# Symposion_K3_Arduino-Peripherie-IF.net
KiCad netlist of a schematic drawn in EAGLE
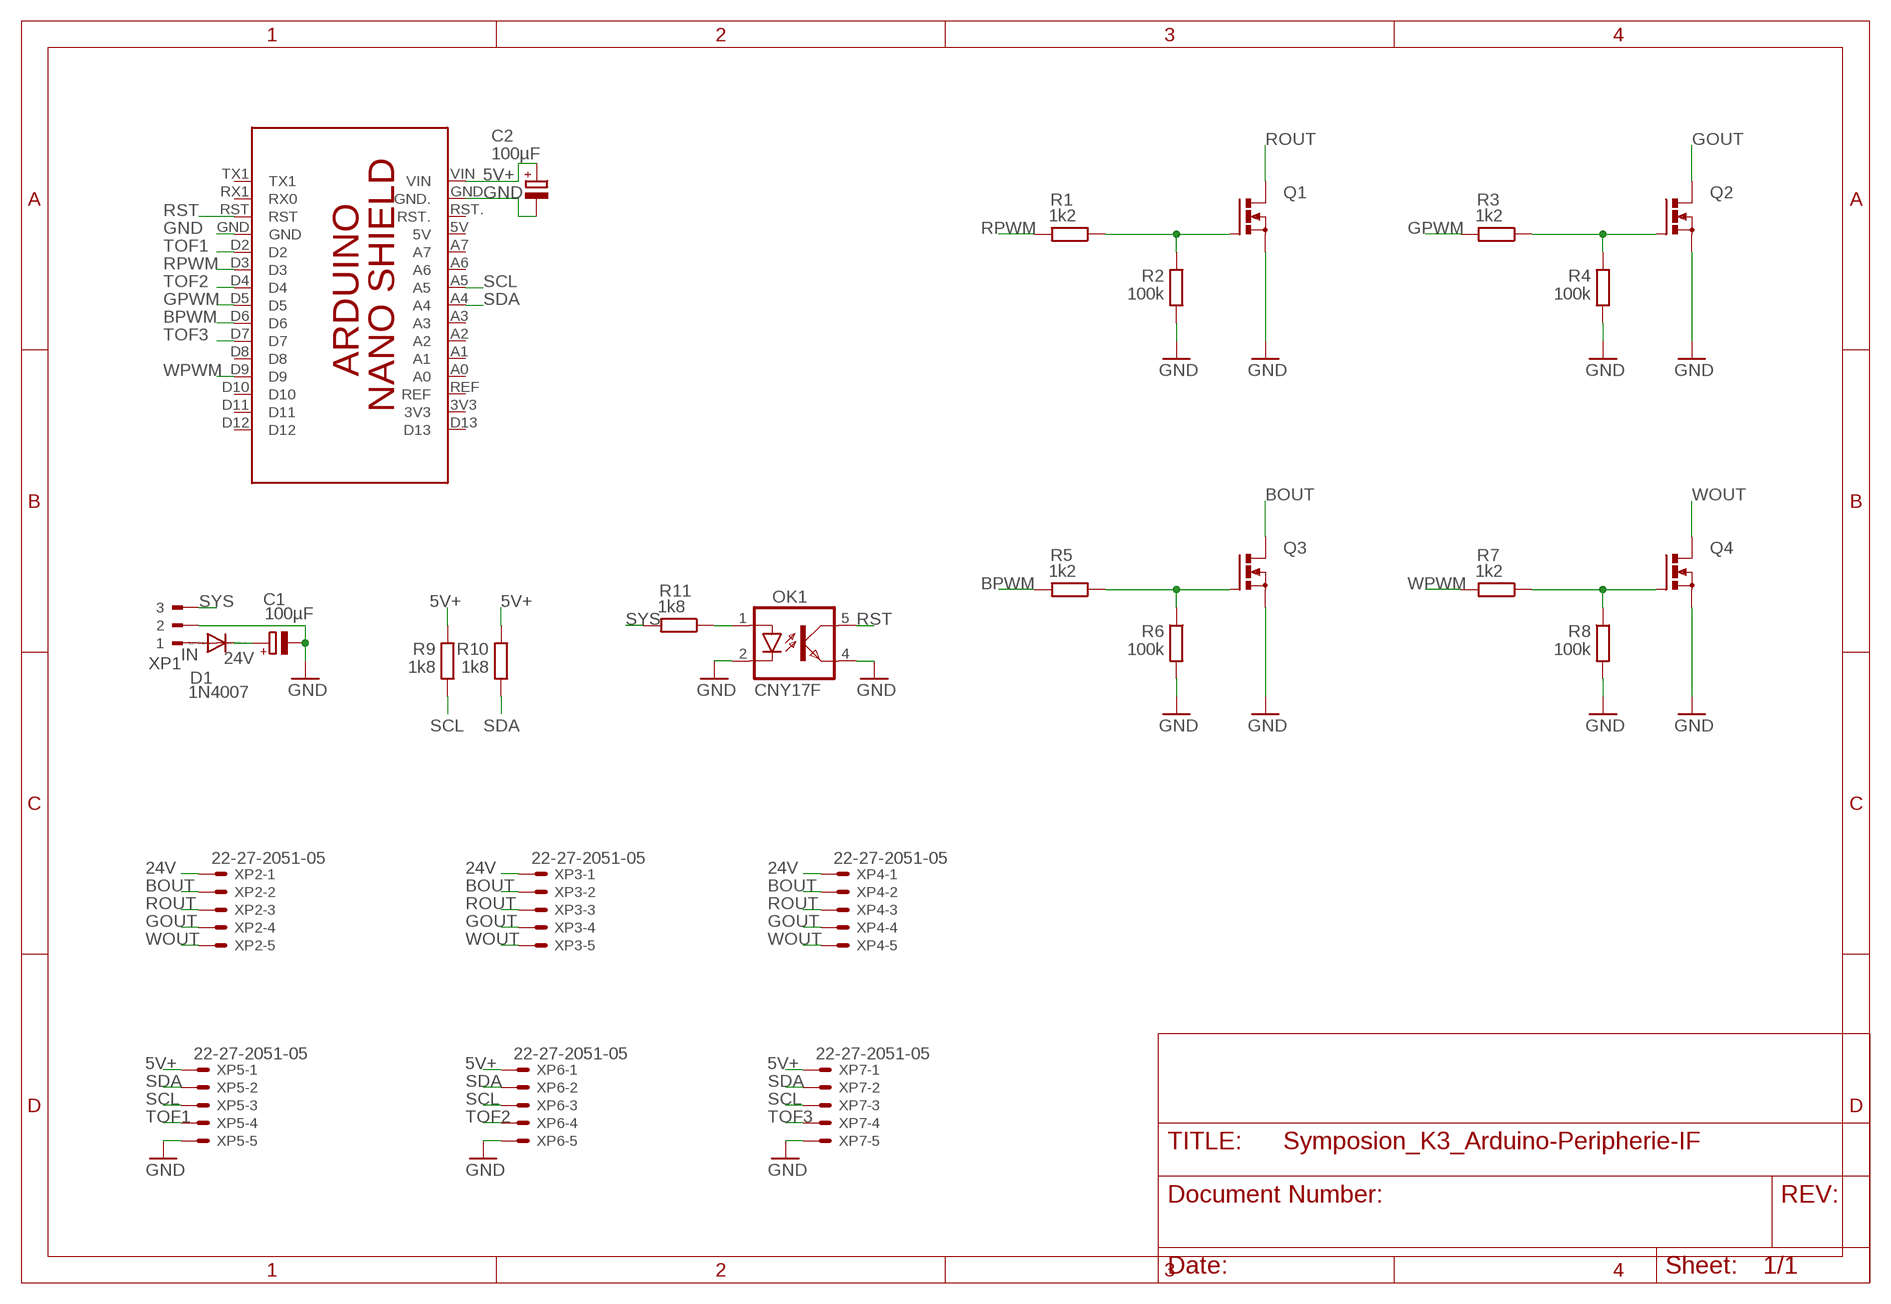
[diagram p0: schematic, sheet 1]

(export (version "E")
  (design (tool "Eeschema 10.0.6"))
  (components
    (comp (ref "C1")
      (value "100µF")
      (footprint "eagle-import:RCL_E5-6")
      (libsource (lib "eagle-import") (part "RCL_CPOL-EUE5-6"))
    )
    (comp (ref "C2")
      (value "100µF")
      (footprint "eagle-import:RCL_E5-6")
      (libsource (lib "eagle-import") (part "RCL_CPOL-EUE5-6"))
    )
    (comp (ref "D1")
      (value "1N4007")
      (footprint "eagle-import:DIODE_F126-10")
      (libsource (lib "eagle-import") (part "DIODE_DIODE-F126-10"))
    )
    (comp (ref "OK1")
      (value "CNY17F")
      (footprint "eagle-import:DIL06")
      (fields (field (name "MF") "VISHAY/TELEFUNKEN") (field (name "MPN") "CNY17F-3"))
      (libsource (lib "eagle-import") (part "CNY17F"))
    )
    (comp (ref "PCB1")
      (value "0_WSH_FAVORITES_ARDUINO_NANO")
      (footprint "eagle-import:0_WSH_FAVORITES_ARDUINO_NANO")
      (libsource (lib "eagle-import") (part "0_WSH_FAVORITES_ARDUINO_NANO"))
    )
    (comp (ref "Q1")
      (value "0_WSH_FAVORITES_BUZ11BV")
      (footprint "eagle-import:0_WSH_FAVORITES_TO220BV")
      (libsource (lib "eagle-import") (part "0_WSH_FAVORITES_BUZ11BV"))
    )
    (comp (ref "Q2")
      (value "0_WSH_FAVORITES_BUZ11BV")
      (footprint "eagle-import:0_WSH_FAVORITES_TO220BV")
      (libsource (lib "eagle-import") (part "0_WSH_FAVORITES_BUZ11BV"))
    )
    (comp (ref "Q3")
      (value "0_WSH_FAVORITES_BUZ11BV")
      (footprint "eagle-import:0_WSH_FAVORITES_TO220BV")
      (libsource (lib "eagle-import") (part "0_WSH_FAVORITES_BUZ11BV"))
    )
    (comp (ref "Q4")
      (value "0_WSH_FAVORITES_BUZ11BV")
      (footprint "eagle-import:0_WSH_FAVORITES_TO220BV")
      (libsource (lib "eagle-import") (part "0_WSH_FAVORITES_BUZ11BV"))
    )
    (comp (ref "R1")
      (value "1k2")
      (footprint "eagle-import:R1206")
      (libsource (lib "eagle-import") (part "R-EU_R1206"))
    )
    (comp (ref "R2")
      (value "100k")
      (footprint "eagle-import:R1206")
      (libsource (lib "eagle-import") (part "R-EU_R1206"))
    )
    (comp (ref "R3")
      (value "1k2")
      (footprint "eagle-import:R1206")
      (libsource (lib "eagle-import") (part "R-EU_R1206"))
    )
    (comp (ref "R4")
      (value "100k")
      (footprint "eagle-import:R1206")
      (libsource (lib "eagle-import") (part "R-EU_R1206"))
    )
    (comp (ref "R5")
      (value "1k2")
      (footprint "eagle-import:R1206")
      (libsource (lib "eagle-import") (part "R-EU_R1206"))
    )
    (comp (ref "R6")
      (value "100k")
      (footprint "eagle-import:R1206")
      (libsource (lib "eagle-import") (part "R-EU_R1206"))
    )
    (comp (ref "R7")
      (value "1k2")
      (footprint "eagle-import:R1206")
      (libsource (lib "eagle-import") (part "R-EU_R1206"))
    )
    (comp (ref "R8")
      (value "100k")
      (footprint "eagle-import:R1206")
      (libsource (lib "eagle-import") (part "R-EU_R1206"))
    )
    (comp (ref "R9")
      (value "1k8")
      (footprint "eagle-import:R1206")
      (libsource (lib "eagle-import") (part "R-EU_R1206"))
    )
    (comp (ref "R10")
      (value "1k8")
      (footprint "eagle-import:R1206")
      (libsource (lib "eagle-import") (part "R-EU_R1206"))
    )
    (comp (ref "R11")
      (value "1k8")
      (footprint "eagle-import:R1206")
      (libsource (lib "eagle-import") (part "R-EU_R1206"))
    )
    (comp (ref "XP1")
      (value "180-3")
      (footprint "eagle-import:180-3")
      (libsource (lib "eagle-import") (part "180-3"))
    )
    (comp (ref "XP2")
      (value "22-27-2051-05")
      (footprint "eagle-import:6410-05")
      (fields (field (name "MF") "MOLEX"))
      (libsource (lib "eagle-import") (part "22-?-0527-2051"))
    )
    (comp (ref "XP3")
      (value "22-27-2051-05")
      (footprint "eagle-import:6410-05")
      (fields (field (name "MF") "MOLEX"))
      (libsource (lib "eagle-import") (part "22-?-0527-2051"))
    )
    (comp (ref "XP4")
      (value "22-27-2051-05")
      (footprint "eagle-import:6410-05")
      (fields (field (name "MF") "MOLEX"))
      (libsource (lib "eagle-import") (part "22-?-0527-2051"))
    )
    (comp (ref "XP5")
      (value "22-27-2051-05")
      (footprint "eagle-import:6410-05")
      (fields (field (name "MF") "MOLEX"))
      (libsource (lib "eagle-import") (part "22-?-0527-2051"))
    )
    (comp (ref "XP6")
      (value "22-27-2051-05")
      (footprint "eagle-import:6410-05")
      (fields (field (name "MF") "MOLEX"))
      (libsource (lib "eagle-import") (part "22-?-0527-2051"))
    )
    (comp (ref "XP7")
      (value "22-27-2051-05")
      (footprint "eagle-import:6410-05")
      (fields (field (name "MF") "MOLEX"))
      (libsource (lib "eagle-import") (part "22-?-0527-2051"))
    )
  )
  (nets
    (net (code "1") (name "/5V+") (class "Default")
      (node (ref "C2") (pin "+") (pinfunction "+_+") (pintype "passive"))
      (node (ref "PCB1") (pin "VIN") (pinfunction "VIN_VIN") (pintype "bidirectional"))
      (node (ref "R10") (pin "1") (pinfunction "1_1") (pintype "passive"))
      (node (ref "R9") (pin "1") (pinfunction "1_1") (pintype "passive"))
      (node (ref "XP5") (pin "1") (pinfunction "S_1") (pintype "passive"))
      (node (ref "XP6") (pin "1") (pinfunction "S_1") (pintype "passive"))
      (node (ref "XP7") (pin "1") (pinfunction "S_1") (pintype "passive"))
    )
    (net (code "2") (name "/24V") (class "Default")
      (node (ref "C1") (pin "+") (pinfunction "+_+") (pintype "passive"))
      (node (ref "D1") (pin "C") (pinfunction "C_C") (pintype "passive"))
      (node (ref "XP2") (pin "1") (pinfunction "S_1") (pintype "passive"))
      (node (ref "XP3") (pin "1") (pinfunction "S_1") (pintype "passive"))
      (node (ref "XP4") (pin "1") (pinfunction "S_1") (pintype "passive"))
    )
    (net (code "3") (name "/BOUT") (class "Default")
      (node (ref "Q3") (pin "D") (pinfunction "D_D") (pintype "passive"))
      (node (ref "XP2") (pin "2") (pinfunction "S_2") (pintype "passive"))
      (node (ref "XP3") (pin "2") (pinfunction "S_2") (pintype "passive"))
      (node (ref "XP4") (pin "2") (pinfunction "S_2") (pintype "passive"))
    )
    (net (code "4") (name "/BPWM") (class "Default")
      (node (ref "PCB1") (pin "D6") (pinfunction "D6_D6") (pintype "bidirectional"))
      (node (ref "R5") (pin "2") (pinfunction "2_2") (pintype "passive"))
    )
    (net (code "5") (name "/GOUT") (class "Default")
      (node (ref "Q2") (pin "D") (pinfunction "D_D") (pintype "passive"))
      (node (ref "XP2") (pin "4") (pinfunction "S_4") (pintype "passive"))
      (node (ref "XP3") (pin "4") (pinfunction "S_4") (pintype "passive"))
      (node (ref "XP4") (pin "4") (pinfunction "S_4") (pintype "passive"))
    )
    (net (code "6") (name "/GPWM") (class "Default")
      (node (ref "PCB1") (pin "D5") (pinfunction "D5_D5") (pintype "bidirectional"))
      (node (ref "R3") (pin "2") (pinfunction "2_2") (pintype "passive"))
    )
    (net (code "8") (name "/ROUT") (class "Default")
      (node (ref "Q1") (pin "D") (pinfunction "D_D") (pintype "passive"))
      (node (ref "XP2") (pin "3") (pinfunction "S_3") (pintype "passive"))
      (node (ref "XP3") (pin "3") (pinfunction "S_3") (pintype "passive"))
      (node (ref "XP4") (pin "3") (pinfunction "S_3") (pintype "passive"))
    )
    (net (code "9") (name "/RPWM") (class "Default")
      (node (ref "PCB1") (pin "D3") (pinfunction "D3_D3") (pintype "bidirectional"))
      (node (ref "R1") (pin "2") (pinfunction "2_2") (pintype "passive"))
    )
    (net (code "10") (name "/RST") (class "Default")
      (node (ref "OK1") (pin "5") (pinfunction "COL_5") (pintype "passive"))
      (node (ref "PCB1") (pin "RST") (pinfunction "RST_RST") (pintype "bidirectional"))
    )
    (net (code "11") (name "/SCL") (class "Default")
      (node (ref "PCB1") (pin "A5") (pinfunction "A5_A5") (pintype "bidirectional"))
      (node (ref "R9") (pin "2") (pinfunction "2_2") (pintype "passive"))
      (node (ref "XP5") (pin "3") (pinfunction "S_3") (pintype "passive"))
      (node (ref "XP6") (pin "3") (pinfunction "S_3") (pintype "passive"))
      (node (ref "XP7") (pin "3") (pinfunction "S_3") (pintype "passive"))
    )
    (net (code "12") (name "/SDA") (class "Default")
      (node (ref "PCB1") (pin "A4") (pinfunction "A4_A4") (pintype "bidirectional"))
      (node (ref "R10") (pin "2") (pinfunction "2_2") (pintype "passive"))
      (node (ref "XP5") (pin "2") (pinfunction "S_2") (pintype "passive"))
      (node (ref "XP6") (pin "2") (pinfunction "S_2") (pintype "passive"))
      (node (ref "XP7") (pin "2") (pinfunction "S_2") (pintype "passive"))
    )
    (net (code "13") (name "/SYS") (class "Default")
      (node (ref "R11") (pin "2") (pinfunction "2_2") (pintype "passive"))
      (node (ref "XP1") (pin "3") (pinfunction "3_3") (pintype "passive"))
    )
    (net (code "14") (name "/TOF1") (class "Default")
      (node (ref "PCB1") (pin "D2") (pinfunction "D2_D2") (pintype "bidirectional"))
      (node (ref "XP5") (pin "4") (pinfunction "S_4") (pintype "passive"))
    )
    (net (code "15") (name "/TOF2") (class "Default")
      (node (ref "PCB1") (pin "D4") (pinfunction "D4_D4") (pintype "bidirectional"))
      (node (ref "XP6") (pin "4") (pinfunction "S_4") (pintype "passive"))
    )
    (net (code "16") (name "/TOF3") (class "Default")
      (node (ref "PCB1") (pin "D7") (pinfunction "D7_D7") (pintype "bidirectional"))
      (node (ref "XP7") (pin "4") (pinfunction "S_4") (pintype "passive"))
    )
    (net (code "17") (name "/WOUT") (class "Default")
      (node (ref "Q4") (pin "D") (pinfunction "D_D") (pintype "passive"))
      (node (ref "XP2") (pin "5") (pinfunction "S_5") (pintype "passive"))
      (node (ref "XP3") (pin "5") (pinfunction "S_5") (pintype "passive"))
      (node (ref "XP4") (pin "5") (pinfunction "S_5") (pintype "passive"))
    )
    (net (code "18") (name "/WPWM") (class "Default")
      (node (ref "PCB1") (pin "D9") (pinfunction "D9_D9") (pintype "bidirectional"))
      (node (ref "R7") (pin "2") (pinfunction "2_2") (pintype "passive"))
    )
    (net (code "19") (name "GND") (class "Default")
      (node (ref "C1") (pin "-") (pinfunction "-_-") (pintype "passive"))
      (node (ref "C2") (pin "-") (pinfunction "-_-") (pintype "passive"))
      (node (ref "OK1") (pin "2") (pinfunction "C_2") (pintype "passive"))
      (node (ref "OK1") (pin "4") (pinfunction "EMIT_4") (pintype "passive"))
      (node (ref "PCB1") (pin "GND") (pinfunction "GND_GND") (pintype "bidirectional"))
      (node (ref "PCB1") (pin "GND.") (pinfunction "GND._GND.") (pintype "bidirectional"))
      (node (ref "Q1") (pin "S") (pinfunction "S_S") (pintype "passive"))
      (node (ref "Q2") (pin "S") (pinfunction "S_S") (pintype "passive"))
      (node (ref "Q3") (pin "S") (pinfunction "S_S") (pintype "passive"))
      (node (ref "Q4") (pin "S") (pinfunction "S_S") (pintype "passive"))
      (node (ref "R2") (pin "2") (pinfunction "2_2") (pintype "passive"))
      (node (ref "R4") (pin "2") (pinfunction "2_2") (pintype "passive"))
      (node (ref "R6") (pin "2") (pinfunction "2_2") (pintype "passive"))
      (node (ref "R8") (pin "2") (pinfunction "2_2") (pintype "passive"))
      (node (ref "XP1") (pin "2") (pinfunction "2_2") (pintype "passive"))
      (node (ref "XP5") (pin "5") (pinfunction "S_5") (pintype "passive"))
      (node (ref "XP6") (pin "5") (pinfunction "S_5") (pintype "passive"))
      (node (ref "XP7") (pin "5") (pinfunction "S_5") (pintype "passive"))
    )
    (net (code "20") (name "Net-(D1-PadA)") (class "Default")
      (node (ref "D1") (pin "A") (pinfunction "A_A") (pintype "passive"))
      (node (ref "XP1") (pin "1") (pinfunction "1_1") (pintype "passive"))
    )
    (net (code "21") (name "Net-(OK1-A)") (class "Default")
      (node (ref "OK1") (pin "1") (pinfunction "A_1") (pintype "passive"))
      (node (ref "R11") (pin "1") (pinfunction "1_1") (pintype "passive"))
    )
    (net (code "22") (name "Net-(Q1-PadG)") (class "Default")
      (node (ref "Q1") (pin "G") (pinfunction "G_G") (pintype "passive"))
      (node (ref "R1") (pin "1") (pinfunction "1_1") (pintype "passive"))
      (node (ref "R2") (pin "1") (pinfunction "1_1") (pintype "passive"))
    )
    (net (code "23") (name "Net-(Q2-PadG)") (class "Default")
      (node (ref "Q2") (pin "G") (pinfunction "G_G") (pintype "passive"))
      (node (ref "R3") (pin "1") (pinfunction "1_1") (pintype "passive"))
      (node (ref "R4") (pin "1") (pinfunction "1_1") (pintype "passive"))
    )
    (net (code "24") (name "Net-(Q3-PadG)") (class "Default")
      (node (ref "Q3") (pin "G") (pinfunction "G_G") (pintype "passive"))
      (node (ref "R5") (pin "1") (pinfunction "1_1") (pintype "passive"))
      (node (ref "R6") (pin "1") (pinfunction "1_1") (pintype "passive"))
    )
    (net (code "25") (name "Net-(Q4-PadG)") (class "Default")
      (node (ref "Q4") (pin "G") (pinfunction "G_G") (pintype "passive"))
      (node (ref "R7") (pin "1") (pinfunction "1_1") (pintype "passive"))
      (node (ref "R8") (pin "1") (pinfunction "1_1") (pintype "passive"))
    )
    (net (code "26") (name "unconnected-(PCB1-Pad3V3)") (class "Default")
      (node (ref "PCB1") (pin "3V3") (pinfunction "3V3_3V3") (pintype "bidirectional"))
    )
    (net (code "27") (name "unconnected-(PCB1-Pad5V)") (class "Default")
      (node (ref "PCB1") (pin "5V") (pinfunction "5V_5V") (pintype "bidirectional"))
    )
    (net (code "28") (name "unconnected-(PCB1-PadA0)") (class "Default")
      (node (ref "PCB1") (pin "A0") (pinfunction "A0_A0") (pintype "bidirectional"))
    )
    (net (code "29") (name "unconnected-(PCB1-PadA1)") (class "Default")
      (node (ref "PCB1") (pin "A1") (pinfunction "A1_A1") (pintype "bidirectional"))
    )
    (net (code "30") (name "unconnected-(PCB1-PadA2)") (class "Default")
      (node (ref "PCB1") (pin "A2") (pinfunction "A2_A2") (pintype "bidirectional"))
    )
    (net (code "31") (name "unconnected-(PCB1-PadA3)") (class "Default")
      (node (ref "PCB1") (pin "A3") (pinfunction "A3_A3") (pintype "bidirectional"))
    )
    (net (code "32") (name "unconnected-(PCB1-PadA6)") (class "Default")
      (node (ref "PCB1") (pin "A6") (pinfunction "A6_A6") (pintype "bidirectional"))
    )
    (net (code "33") (name "unconnected-(PCB1-PadA7)") (class "Default")
      (node (ref "PCB1") (pin "A7") (pinfunction "A7_A7") (pintype "bidirectional"))
    )
    (net (code "34") (name "unconnected-(PCB1-PadD8)") (class "Default")
      (node (ref "PCB1") (pin "D8") (pinfunction "D8_D8") (pintype "bidirectional"))
    )
    (net (code "35") (name "unconnected-(PCB1-PadD10)") (class "Default")
      (node (ref "PCB1") (pin "D10") (pinfunction "D10_D10") (pintype "bidirectional"))
    )
    (net (code "36") (name "unconnected-(PCB1-PadD11)") (class "Default")
      (node (ref "PCB1") (pin "D11") (pinfunction "D11_D11") (pintype "bidirectional"))
    )
    (net (code "37") (name "unconnected-(PCB1-PadD12)") (class "Default")
      (node (ref "PCB1") (pin "D12") (pinfunction "D12_D12") (pintype "bidirectional"))
    )
    (net (code "38") (name "unconnected-(PCB1-PadD13)") (class "Default")
      (node (ref "PCB1") (pin "D13") (pinfunction "D13_D13") (pintype "bidirectional"))
    )
    (net (code "39") (name "unconnected-(PCB1-PadREF)") (class "Default")
      (node (ref "PCB1") (pin "REF") (pinfunction "REF_REF") (pintype "bidirectional"))
    )
    (net (code "40") (name "unconnected-(PCB1-PadRST.)") (class "Default")
      (node (ref "PCB1") (pin "RST.") (pinfunction "RST._RST.") (pintype "bidirectional"))
    )
    (net (code "41") (name "unconnected-(PCB1-PadTX1)") (class "Default")
      (node (ref "PCB1") (pin "TX1") (pinfunction "TX1_TX1") (pintype "bidirectional"))
    )
    (net (code "42") (name "unconnected-(PCB1-RX0-PadRX1)") (class "Default")
      (node (ref "PCB1") (pin "RX1") (pinfunction "RX0_RX1") (pintype "bidirectional"))
    )
  )
)
